# RasPi-BplusHAT-RELAY.net
KiCad netlist of a schematic drawn in Altium Designer
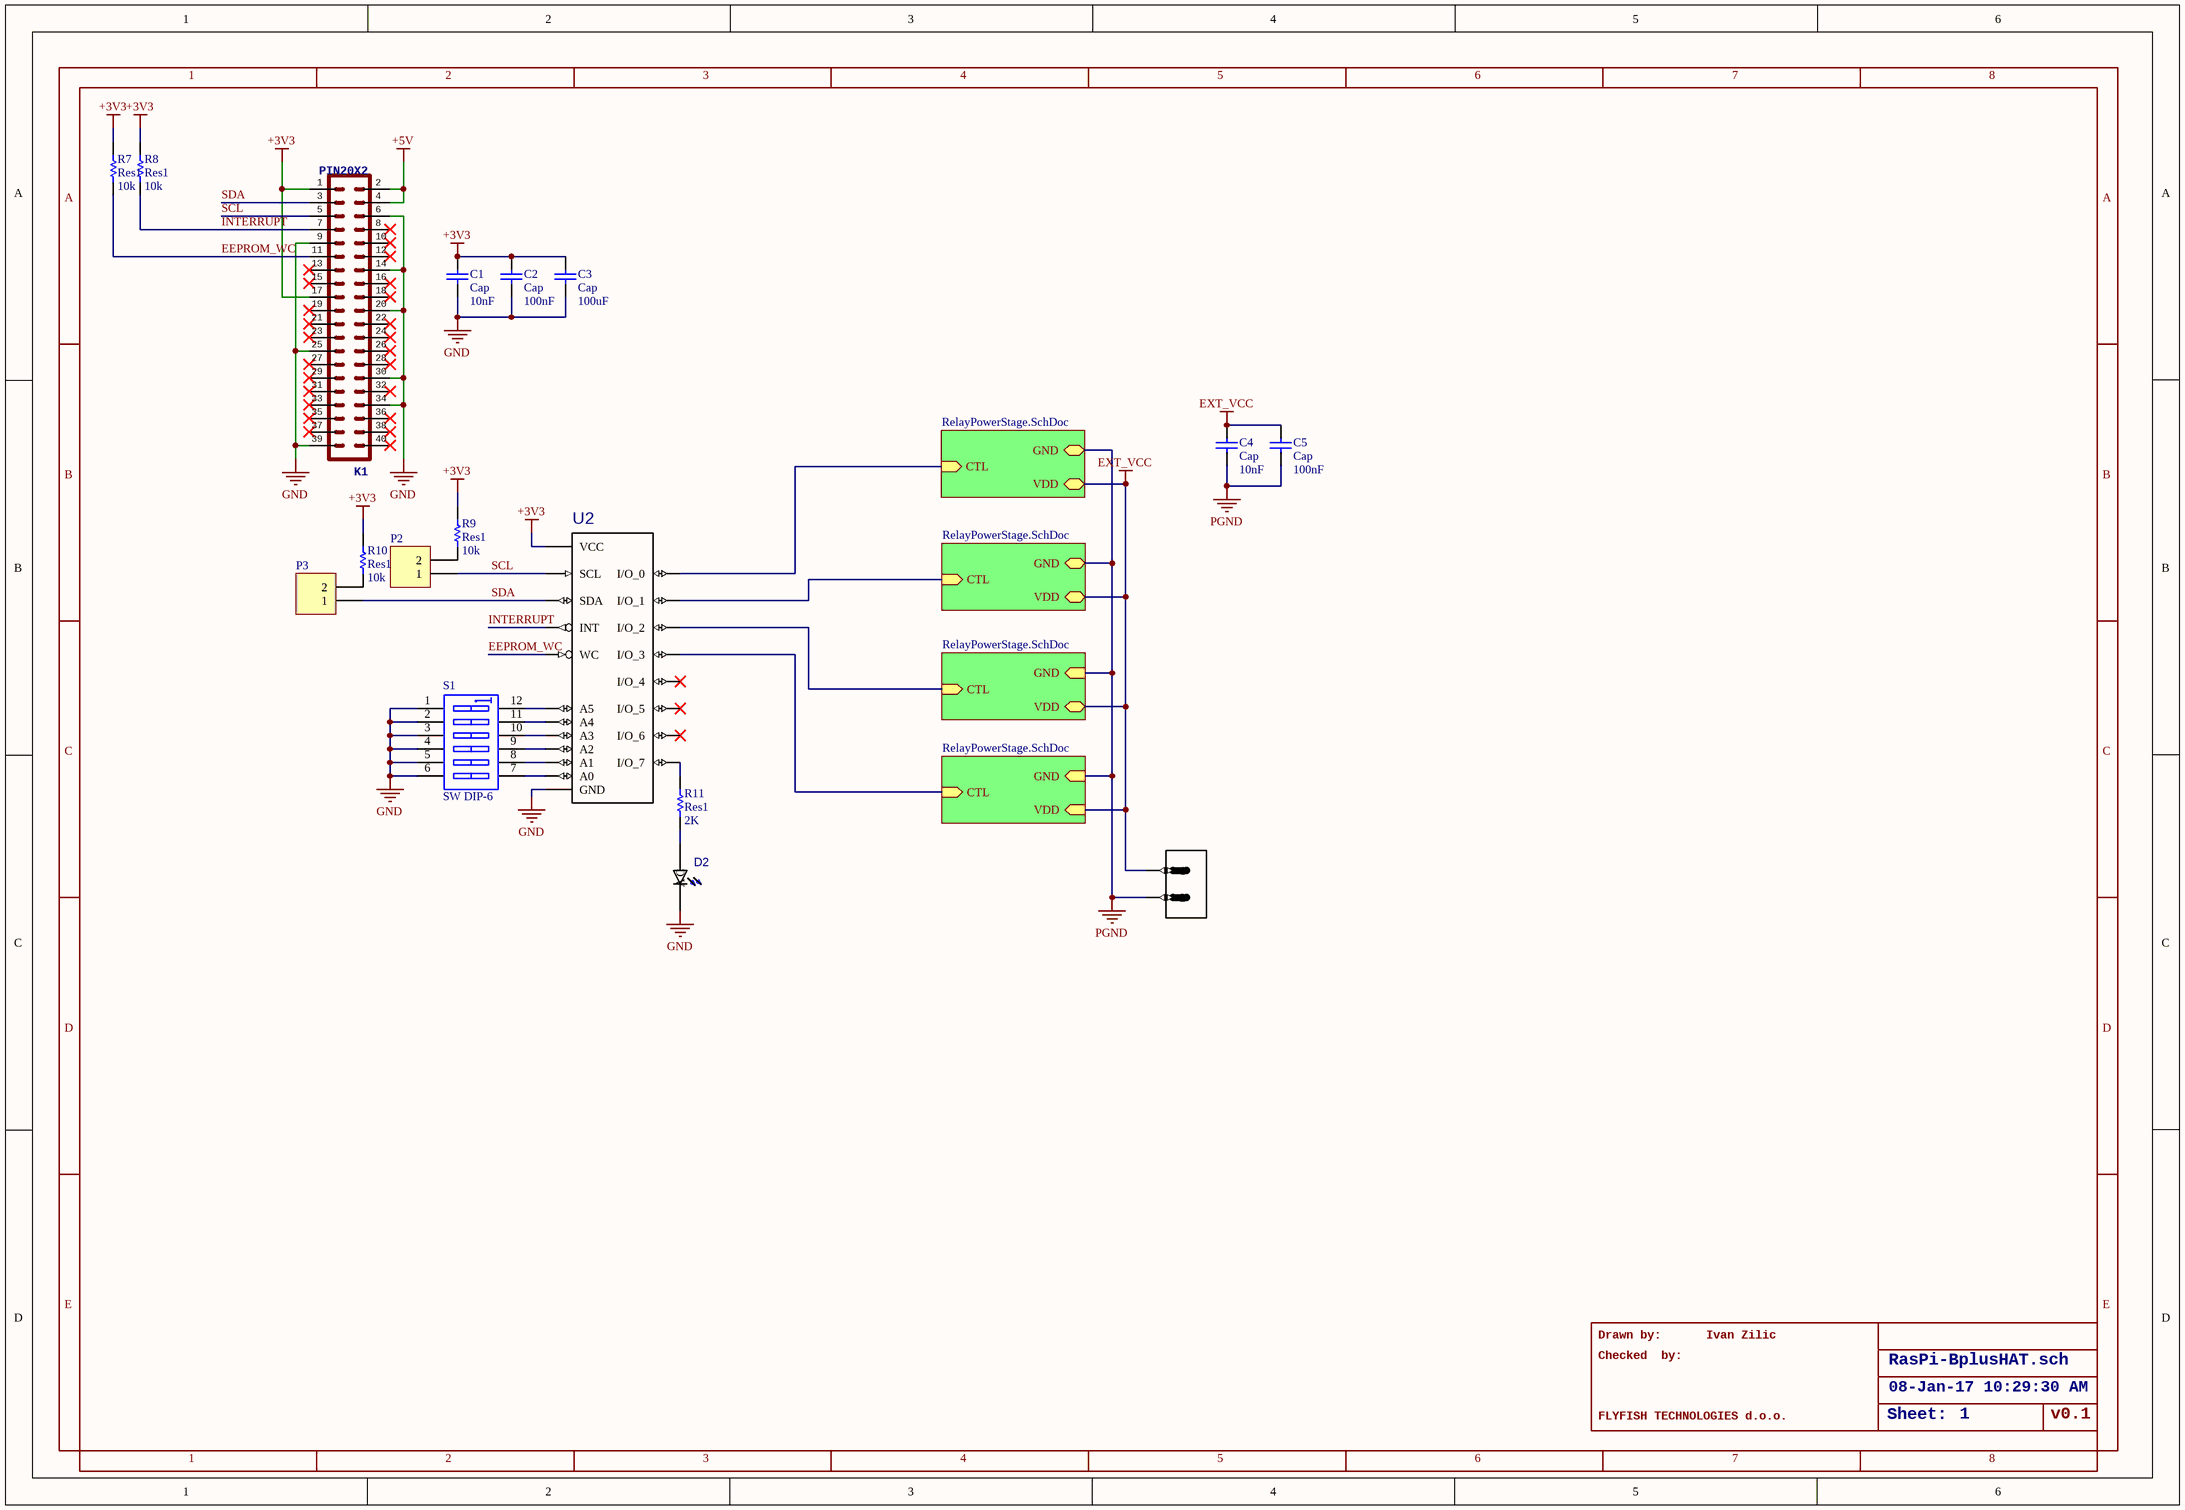
[diagram p0: RasPi-BplusHAT-RELAY.SchDoc]

(export (version "E")
  (design (tool "Eeschema 10.0.6"))
  (components
    (comp (ref "C1")
      (value "Cap")
      (footprint "6-0805_N")
      (description "Capacitor")
      (fields (field (name "ALTIUM_VALUE") "10nF") (field (name "PUBLISHER") "Altium Limited"))
      (libsource (lib "Miscellaneous Devices") (part "Cap"))
    )
    (comp (ref "C2")
      (value "Cap")
      (footprint "6-0805_N")
      (description "Capacitor")
      (fields (field (name "ALTIUM_VALUE") "100nF") (field (name "PUBLISHER") "Altium Limited"))
      (libsource (lib "Miscellaneous Devices") (part "Cap"))
    )
    (comp (ref "C3")
      (value "Cap")
      (footprint "6-0805_N")
      (description "Capacitor")
      (fields (field (name "ALTIUM_VALUE") "100uF") (field (name "PUBLISHER") "Altium Limited"))
      (libsource (lib "Miscellaneous Devices") (part "Cap"))
    )
    (comp (ref "C4")
      (value "Cap")
      (footprint "6-0805_N")
      (description "Capacitor")
      (fields (field (name "ALTIUM_VALUE") "10nF") (field (name "PUBLISHER") "Altium Limited"))
      (libsource (lib "Miscellaneous Devices") (part "Cap"))
    )
    (comp (ref "C5")
      (value "Cap")
      (footprint "6-0805_N")
      (description "Capacitor")
      (fields (field (name "ALTIUM_VALUE") "100nF") (field (name "PUBLISHER") "Altium Limited"))
      (libsource (lib "Miscellaneous Devices") (part "Cap"))
    )
    (comp (ref "D2")
      (value "0805_LED")
      (footprint "LEDSC200X125X70-2N_598-8160-107F(Primary)")
      (description "LED, SMD; 0805; Yellow-Green; Water Clear Lens; 40mcd; 570/575nm")
      (fields (field (name "MP") "598-8160-107F") (field (name "MF") "Dialight"))
      (libsource (lib "0805_LED") (part "598-8160-107F"))
    )
    (comp (ref "J2")
      (value "1760510000")
      (footprint "1760490000")
      (description "Conn Terminal Block 2 POS 5.08mm Solder ST Thru-Hole 16A")
      (fields (field (name "MF") "Weidmuller"))
      (libsource (lib "1760510000") (part "1760510000"))
    )
    (comp (ref "K1")
      (value "PIN20X2")
      (footprint "HDR2X20")
      (fields (field (name ">VALUE") "PIN20X2") (field (name ">NAME") "K1"))
      (libsource (lib "FLYFISH") (part "PIN20X2"))
    )
    (comp (ref "P2")
      (value "Header 2")
      (footprint "HDR1X2")
      (description "Header, 2-Pin")
      (fields (field (name "PUBLISHER") "Altium Limited"))
      (libsource (lib "Miscellaneous Connectors") (part "Header 2"))
    )
    (comp (ref "P3")
      (value "Header 2")
      (footprint "HDR1X2")
      (description "Header, 2-Pin")
      (fields (field (name "PUBLISHER") "Altium Limited"))
      (libsource (lib "Miscellaneous Connectors") (part "Header 2"))
    )
    (comp (ref "R7")
      (value "Res1")
      (footprint "6-0805_N")
      (description "Resistor")
      (fields (field (name "ALTIUM_VALUE") "10k") (field (name "PUBLISHER") "Altium Limited"))
      (libsource (lib "Miscellaneous Devices") (part "Res1"))
    )
    (comp (ref "R8")
      (value "Res1")
      (footprint "6-0805_N")
      (description "Resistor")
      (fields (field (name "ALTIUM_VALUE") "10k") (field (name "PUBLISHER") "Altium Limited"))
      (libsource (lib "Miscellaneous Devices") (part "Res1"))
    )
    (comp (ref "R9")
      (value "Res1")
      (footprint "6-0805_N")
      (description "Resistor")
      (fields (field (name "ALTIUM_VALUE") "10k") (field (name "PUBLISHER") "Altium Limited"))
      (libsource (lib "Miscellaneous Devices") (part "Res1"))
    )
    (comp (ref "R10")
      (value "Res1")
      (footprint "6-0805_N")
      (description "Resistor")
      (fields (field (name "ALTIUM_VALUE") "10k") (field (name "PUBLISHER") "Altium Limited"))
      (libsource (lib "Miscellaneous Devices") (part "Res1"))
    )
    (comp (ref "R11")
      (value "Res1")
      (footprint "6-0805_N")
      (description "Resistor")
      (fields (field (name "ALTIUM_VALUE") "2K") (field (name "PUBLISHER") "Altium Limited"))
      (libsource (lib "Miscellaneous Devices") (part "Res1"))
    )
    (comp (ref "S1")
      (value "SW DIP-6")
      (footprint "DIP-12/SW")
      (description "DIP Switch, 6 Position, SPST")
      (fields (field (name "PUBLISHER") "Altium Limited"))
      (libsource (lib "Miscellaneous Devices") (part "SW DIP-6"))
    )
    (comp (ref "U2")
      (value "PCA9501")
      (footprint "TSSOP20")
      (fields (field (name "MF") "NXP Semiconductors"))
      (libsource (lib "PCA9501") (part "PCA9501"))
    )
  )
  (nets
    (net (code "1") (name "+3V3") (class "Default")
      (node (ref "C1") (pin "2") (pinfunction "2_2") (pintype "passive"))
      (node (ref "C2") (pin "2") (pinfunction "2_2") (pintype "passive"))
      (node (ref "C3") (pin "2") (pinfunction "2_2") (pintype "passive"))
      (node (ref "K1") (pin "1") (pinfunction "1_1") (pintype "passive"))
      (node (ref "K1") (pin "17") (pinfunction "17_17") (pintype "passive"))
      (node (ref "R10") (pin "1") (pinfunction "1_1") (pintype "passive"))
      (node (ref "R7") (pin "1") (pinfunction "1_1") (pintype "passive"))
      (node (ref "R8") (pin "1") (pinfunction "1_1") (pintype "passive"))
      (node (ref "R9") (pin "1") (pinfunction "1_1") (pintype "passive"))
      (node (ref "U2") (pin "20") (pinfunction "VCC_20") (pintype "power_in"))
    )
    (net (code "2") (name "+5V") (class "Default")
      (node (ref "K1") (pin "2") (pinfunction "2_2") (pintype "passive"))
      (node (ref "K1") (pin "4") (pinfunction "4_4") (pintype "passive"))
    )
    (net (code "3") (name "/CTL") (class "Default")
      (node (ref "U2") (pin "6") (pinfunction "I/O_2_6") (pintype "bidirectional"))
    )
    (net (code "4") (name "/CTL_1") (class "Default")
      (node (ref "U2") (pin "7") (pinfunction "I/O_3_7") (pintype "bidirectional"))
    )
    (net (code "5") (name "/CTL_2") (class "Default")
      (node (ref "U2") (pin "4") (pinfunction "I/O_0_4") (pintype "bidirectional"))
    )
    (net (code "6") (name "/CTL_3") (class "Default")
      (node (ref "U2") (pin "5") (pinfunction "I/O_1_5") (pintype "bidirectional"))
    )
    (net (code "7") (name "/EEPROM_WC") (class "Default")
      (node (ref "K1") (pin "11") (pinfunction "11_11") (pintype "passive"))
      (node (ref "R7") (pin "2") (pinfunction "2_2") (pintype "passive"))
      (node (ref "U2") (pin "17") (pinfunction "WC_17") (pintype "input"))
    )
    (net (code "8") (name "/INTERRUPT") (class "Default")
      (node (ref "K1") (pin "7") (pinfunction "7_7") (pintype "passive"))
      (node (ref "R8") (pin "2") (pinfunction "2_2") (pintype "passive"))
      (node (ref "U2") (pin "8") (pinfunction "INT_8") (pintype "output"))
    )
    (net (code "9") (name "/SCL") (class "Default")
      (node (ref "K1") (pin "5") (pinfunction "5_5") (pintype "passive"))
      (node (ref "P2") (pin "1") (pinfunction "1_1") (pintype "passive"))
      (node (ref "U2") (pin "18") (pinfunction "SCL_18") (pintype "input"))
    )
    (net (code "10") (name "/SDA") (class "Default")
      (node (ref "K1") (pin "3") (pinfunction "3_3") (pintype "passive"))
      (node (ref "P3") (pin "1") (pinfunction "1_1") (pintype "passive"))
      (node (ref "U2") (pin "19") (pinfunction "SDA_19") (pintype "bidirectional"))
    )
    (net (code "11") (name "EXT_VCC") (class "Default")
      (node (ref "C4") (pin "2") (pinfunction "2_2") (pintype "passive"))
      (node (ref "C5") (pin "2") (pinfunction "2_2") (pintype "passive"))
      (node (ref "J2") (pin "1") (pinfunction "1_1") (pintype "bidirectional"))
    )
    (net (code "12") (name "GND") (class "Default")
      (node (ref "C1") (pin "1") (pinfunction "1_1") (pintype "passive"))
      (node (ref "C2") (pin "1") (pinfunction "1_1") (pintype "passive"))
      (node (ref "C3") (pin "1") (pinfunction "1_1") (pintype "passive"))
      (node (ref "D2") (pin "C") (pinfunction "C_C") (pintype "passive"))
      (node (ref "K1") (pin "14") (pinfunction "14_14") (pintype "passive"))
      (node (ref "K1") (pin "20") (pinfunction "20_20") (pintype "passive"))
      (node (ref "K1") (pin "25") (pinfunction "25_25") (pintype "passive"))
      (node (ref "K1") (pin "30") (pinfunction "30_30") (pintype "passive"))
      (node (ref "K1") (pin "34") (pinfunction "34_34") (pintype "passive"))
      (node (ref "K1") (pin "39") (pinfunction "39_39") (pintype "passive"))
      (node (ref "K1") (pin "6") (pinfunction "6_6") (pintype "passive"))
      (node (ref "K1") (pin "9") (pinfunction "9_9") (pintype "passive"))
      (node (ref "S1") (pin "1") (pinfunction "A1_1") (pintype "passive"))
      (node (ref "S1") (pin "2") (pinfunction "A2_2") (pintype "passive"))
      (node (ref "S1") (pin "3") (pinfunction "A3_3") (pintype "passive"))
      (node (ref "S1") (pin "4") (pinfunction "A4_4") (pintype "passive"))
      (node (ref "S1") (pin "5") (pinfunction "A5_5") (pintype "passive"))
      (node (ref "S1") (pin "6") (pinfunction "A6_6") (pintype "passive"))
      (node (ref "U2") (pin "10") (pinfunction "GND_10") (pintype "power_in"))
    )
    (net (code "13") (name "Net-(D2-PadA)") (class "Default")
      (node (ref "D2") (pin "A") (pinfunction "A_A") (pintype "passive"))
      (node (ref "R11") (pin "2") (pinfunction "2_2") (pintype "passive"))
    )
    (net (code "14") (name "Net-(P2-Pad2)") (class "Default")
      (node (ref "P2") (pin "2") (pinfunction "2_2") (pintype "passive"))
      (node (ref "R9") (pin "2") (pinfunction "2_2") (pintype "passive"))
    )
    (net (code "15") (name "Net-(P3-Pad2)") (class "Default")
      (node (ref "P3") (pin "2") (pinfunction "2_2") (pintype "passive"))
      (node (ref "R10") (pin "2") (pinfunction "2_2") (pintype "passive"))
    )
    (net (code "16") (name "Net-(S1-B1)") (class "Default")
      (node (ref "S1") (pin "12") (pinfunction "B1_12") (pintype "passive"))
      (node (ref "U2") (pin "9") (pinfunction "A5_9") (pintype "bidirectional"))
    )
    (net (code "17") (name "Net-(S1-B2)") (class "Default")
      (node (ref "S1") (pin "11") (pinfunction "B2_11") (pintype "passive"))
      (node (ref "U2") (pin "11") (pinfunction "A4_11") (pintype "bidirectional"))
    )
    (net (code "18") (name "Net-(S1-B3)") (class "Default")
      (node (ref "S1") (pin "10") (pinfunction "B3_10") (pintype "passive"))
      (node (ref "U2") (pin "12") (pinfunction "A3_12") (pintype "bidirectional"))
    )
    (net (code "19") (name "Net-(S1-B4)") (class "Default")
      (node (ref "S1") (pin "9") (pinfunction "B4_9") (pintype "passive"))
      (node (ref "U2") (pin "3") (pinfunction "A2_3") (pintype "bidirectional"))
    )
    (net (code "20") (name "Net-(S1-B5)") (class "Default")
      (node (ref "S1") (pin "8") (pinfunction "B5_8") (pintype "passive"))
      (node (ref "U2") (pin "2") (pinfunction "A1_2") (pintype "bidirectional"))
    )
    (net (code "21") (name "Net-(S1-B6)") (class "Default")
      (node (ref "S1") (pin "7") (pinfunction "B6_7") (pintype "passive"))
      (node (ref "U2") (pin "1") (pinfunction "A0_1") (pintype "bidirectional"))
    )
    (net (code "22") (name "Net-(U2-I{slash}O_7)") (class "Default")
      (node (ref "R11") (pin "1") (pinfunction "1_1") (pintype "passive"))
      (node (ref "U2") (pin "16") (pinfunction "I/O_7_16") (pintype "bidirectional"))
    )
    (net (code "23") (name "PGND") (class "Default")
      (node (ref "C4") (pin "1") (pinfunction "1_1") (pintype "passive"))
      (node (ref "C5") (pin "1") (pinfunction "1_1") (pintype "passive"))
      (node (ref "J2") (pin "2") (pinfunction "2_2") (pintype "bidirectional"))
    )
    (net (code "24") (name "unconnected-(K1-Pad8)") (class "Default")
      (node (ref "K1") (pin "8") (pinfunction "8_8") (pintype "passive+no_connect"))
    )
    (net (code "25") (name "unconnected-(K1-Pad10)") (class "Default")
      (node (ref "K1") (pin "10") (pinfunction "10_10") (pintype "passive+no_connect"))
    )
    (net (code "26") (name "unconnected-(K1-Pad12)") (class "Default")
      (node (ref "K1") (pin "12") (pinfunction "12_12") (pintype "passive+no_connect"))
    )
    (net (code "27") (name "unconnected-(K1-Pad13)") (class "Default")
      (node (ref "K1") (pin "13") (pinfunction "13_13") (pintype "passive+no_connect"))
    )
    (net (code "28") (name "unconnected-(K1-Pad15)") (class "Default")
      (node (ref "K1") (pin "15") (pinfunction "15_15") (pintype "passive+no_connect"))
    )
    (net (code "29") (name "unconnected-(K1-Pad16)") (class "Default")
      (node (ref "K1") (pin "16") (pinfunction "16_16") (pintype "passive+no_connect"))
    )
    (net (code "30") (name "unconnected-(K1-Pad18)") (class "Default")
      (node (ref "K1") (pin "18") (pinfunction "18_18") (pintype "passive+no_connect"))
    )
    (net (code "31") (name "unconnected-(K1-Pad19)") (class "Default")
      (node (ref "K1") (pin "19") (pinfunction "19_19") (pintype "passive+no_connect"))
    )
    (net (code "32") (name "unconnected-(K1-Pad21)") (class "Default")
      (node (ref "K1") (pin "21") (pinfunction "21_21") (pintype "passive+no_connect"))
    )
    (net (code "33") (name "unconnected-(K1-Pad22)") (class "Default")
      (node (ref "K1") (pin "22") (pinfunction "22_22") (pintype "passive+no_connect"))
    )
    (net (code "34") (name "unconnected-(K1-Pad23)") (class "Default")
      (node (ref "K1") (pin "23") (pinfunction "23_23") (pintype "passive+no_connect"))
    )
    (net (code "35") (name "unconnected-(K1-Pad24)") (class "Default")
      (node (ref "K1") (pin "24") (pinfunction "24_24") (pintype "passive+no_connect"))
    )
    (net (code "36") (name "unconnected-(K1-Pad26)") (class "Default")
      (node (ref "K1") (pin "26") (pinfunction "26_26") (pintype "passive+no_connect"))
    )
    (net (code "37") (name "unconnected-(K1-Pad27)") (class "Default")
      (node (ref "K1") (pin "27") (pinfunction "27_27") (pintype "passive+no_connect"))
    )
    (net (code "38") (name "unconnected-(K1-Pad28)") (class "Default")
      (node (ref "K1") (pin "28") (pinfunction "28_28") (pintype "passive+no_connect"))
    )
    (net (code "39") (name "unconnected-(K1-Pad29)") (class "Default")
      (node (ref "K1") (pin "29") (pinfunction "29_29") (pintype "passive+no_connect"))
    )
    (net (code "40") (name "unconnected-(K1-Pad31)") (class "Default")
      (node (ref "K1") (pin "31") (pinfunction "31_31") (pintype "passive+no_connect"))
    )
    (net (code "41") (name "unconnected-(K1-Pad32)") (class "Default")
      (node (ref "K1") (pin "32") (pinfunction "32_32") (pintype "passive+no_connect"))
    )
    (net (code "42") (name "unconnected-(K1-Pad33)") (class "Default")
      (node (ref "K1") (pin "33") (pinfunction "33_33") (pintype "passive+no_connect"))
    )
    (net (code "43") (name "unconnected-(K1-Pad35)") (class "Default")
      (node (ref "K1") (pin "35") (pinfunction "35_35") (pintype "passive+no_connect"))
    )
    (net (code "44") (name "unconnected-(K1-Pad36)") (class "Default")
      (node (ref "K1") (pin "36") (pinfunction "36_36") (pintype "passive+no_connect"))
    )
    (net (code "45") (name "unconnected-(K1-Pad37)") (class "Default")
      (node (ref "K1") (pin "37") (pinfunction "37_37") (pintype "passive+no_connect"))
    )
    (net (code "46") (name "unconnected-(K1-Pad38)") (class "Default")
      (node (ref "K1") (pin "38") (pinfunction "38_38") (pintype "passive+no_connect"))
    )
    (net (code "47") (name "unconnected-(K1-Pad40)") (class "Default")
      (node (ref "K1") (pin "40") (pinfunction "40_40") (pintype "passive+no_connect"))
    )
    (net (code "48") (name "unconnected-(U2-I{slash}O_4-Pad13)") (class "Default")
      (node (ref "U2") (pin "13") (pinfunction "I/O_4_13") (pintype "bidirectional+no_connect"))
    )
    (net (code "49") (name "unconnected-(U2-I{slash}O_5-Pad14)") (class "Default")
      (node (ref "U2") (pin "14") (pinfunction "I/O_5_14") (pintype "bidirectional+no_connect"))
    )
    (net (code "50") (name "unconnected-(U2-I{slash}O_6-Pad15)") (class "Default")
      (node (ref "U2") (pin "15") (pinfunction "I/O_6_15") (pintype "bidirectional+no_connect"))
    )
  )
)
